# OSO-SWAT-A1-05.net
KiCad netlist of a schematic drawn in EAGLE
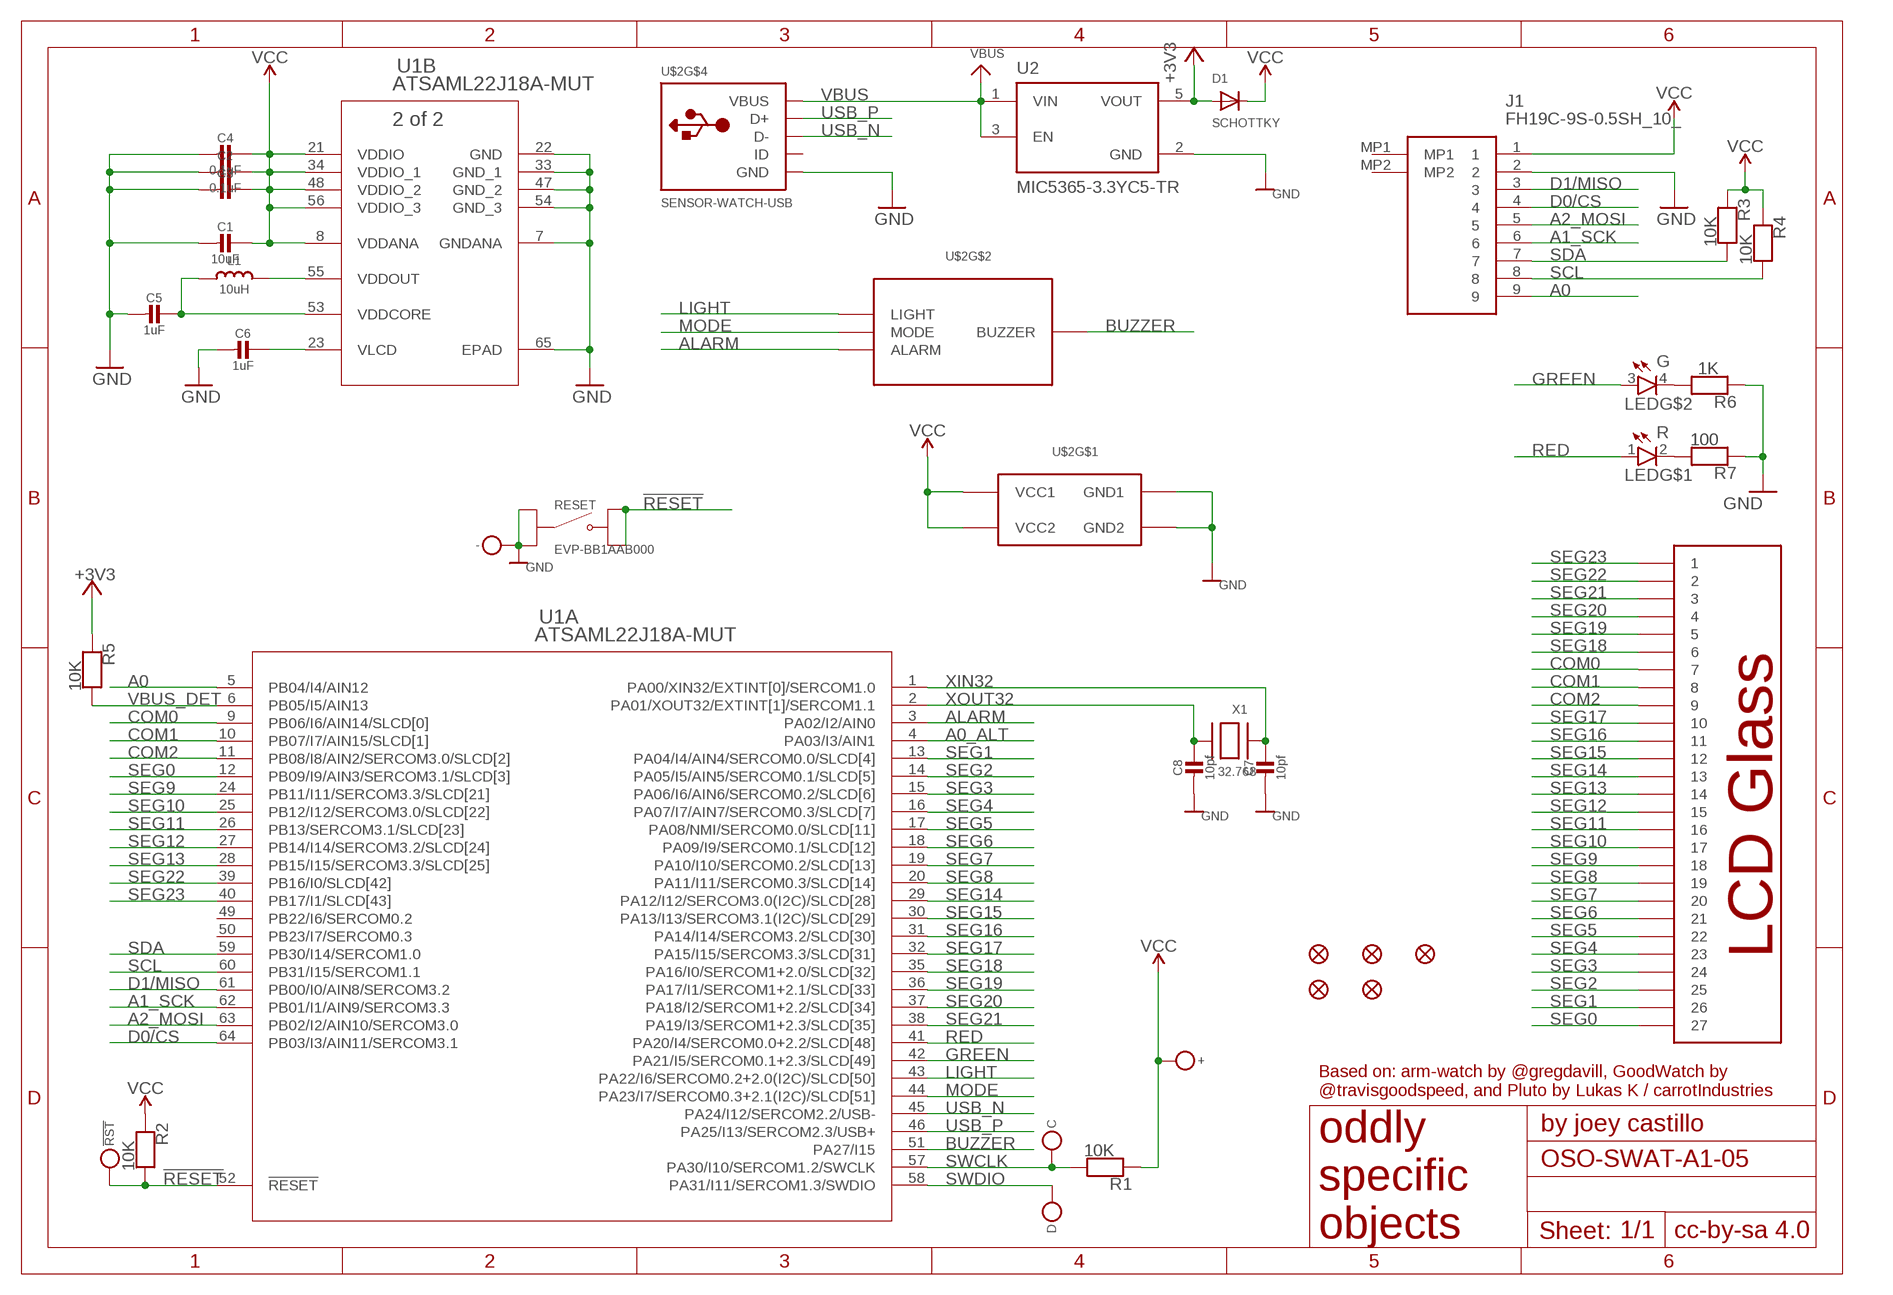
[diagram p0: schematic, sheet 1]

(export (version "E")
  (design (tool "Eeschema 10.0.6"))
  (components
    (comp (ref "!RST")
      (value "MICROBUILDER_TESTPOINTROUND1.5MM")
      (footprint "eagle-import:MICROBUILDER_TESTPOINT_ROUND_1.5MM")
      (libsource (lib "eagle-import") (part "MICROBUILDER_TESTPOINTROUND1.5MM"))
    )
    (comp (ref "+")
      (value "MICROBUILDER_TESTPOINTROUND1.5MM")
      (footprint "eagle-import:MICROBUILDER_TESTPOINT_ROUND_1.5MM")
      (libsource (lib "eagle-import") (part "MICROBUILDER_TESTPOINTROUND1.5MM"))
    )
    (comp (ref "-")
      (value "MICROBUILDER_TESTPOINTROUND1.5MM")
      (footprint "eagle-import:MICROBUILDER_TESTPOINT_ROUND_1.5MM")
      (libsource (lib "eagle-import") (part "MICROBUILDER_TESTPOINTROUND1.5MM"))
    )
    (comp (ref "C")
      (value "MICROBUILDER_TESTPOINTROUND1.5MM")
      (footprint "eagle-import:MICROBUILDER_TESTPOINT_ROUND_1.5MM")
      (libsource (lib "eagle-import") (part "MICROBUILDER_TESTPOINTROUND1.5MM"))
    )
    (comp (ref "C1")
      (value "10uF")
      (footprint "eagle-import:_0603MP")
      (libsource (lib "eagle-import") (part "CAP_CERAMIC_0603MP"))
    )
    (comp (ref "C2")
      (value "0.1uF")
      (footprint "eagle-import:_0603MP")
      (libsource (lib "eagle-import") (part "CAP_CERAMIC_0603MP"))
    )
    (comp (ref "C3")
      (value "0.1uF")
      (footprint "eagle-import:_0603MP")
      (libsource (lib "eagle-import") (part "CAP_CERAMIC_0603MP"))
    )
    (comp (ref "C4")
      (value "0.1uF")
      (footprint "eagle-import:_0603MP")
      (libsource (lib "eagle-import") (part "CAP_CERAMIC_0603MP"))
    )
    (comp (ref "C5")
      (value "1uF")
      (footprint "eagle-import:_0603MP")
      (libsource (lib "eagle-import") (part "CAP_CERAMIC_0603MP"))
    )
    (comp (ref "C6")
      (value "1uF")
      (footprint "eagle-import:_0603MP")
      (libsource (lib "eagle-import") (part "CAP_CERAMIC_0603MP"))
    )
    (comp (ref "C7")
      (value "10pf")
      (footprint "eagle-import:_0402MP")
      (libsource (lib "eagle-import") (part "CAP_CERAMIC_0402MP"))
    )
    (comp (ref "C8")
      (value "10pf")
      (footprint "eagle-import:_0402MP")
      (libsource (lib "eagle-import") (part "CAP_CERAMIC_0402MP"))
    )
    (comp (ref "D")
      (value "MICROBUILDER_TESTPOINTROUND1.5MM")
      (footprint "eagle-import:MICROBUILDER_TESTPOINT_ROUND_1.5MM")
      (libsource (lib "eagle-import") (part "MICROBUILDER_TESTPOINTROUND1.5MM"))
    )
    (comp (ref "D1")
      (value "SCHOTTKY")
      (footprint "eagle-import:SOD-323F")
      (libsource (lib "eagle-import") (part "DIODESOD-323F"))
    )
    (comp (ref "FID1")
      (value "FIDUCIAL_1MM")
      (footprint "eagle-import:FIDUCIAL_1MM")
      (libsource (lib "eagle-import") (part "FIDUCIAL_1MM"))
    )
    (comp (ref "FID2")
      (value "FIDUCIAL_1MM")
      (footprint "eagle-import:FIDUCIAL_1MM")
      (libsource (lib "eagle-import") (part "FIDUCIAL_1MM"))
    )
    (comp (ref "FID3")
      (value "FIDUCIAL_1MM")
      (footprint "eagle-import:FIDUCIAL_1MM")
      (fields (field (name "REV") "A"))
      (libsource (lib "eagle-import") (part "FIDUCIAL_1MM"))
    )
    (comp (ref "FID4")
      (value "FIDUCIAL_1MM")
      (footprint "eagle-import:FIDUCIAL_1MM")
      (libsource (lib "eagle-import") (part "FIDUCIAL_1MM"))
    )
    (comp (ref "FID6")
      (value "FIDUCIAL_1MM")
      (footprint "eagle-import:FIDUCIAL_1MM")
      (fields (field (name "REV") "A"))
      (libsource (lib "eagle-import") (part "FIDUCIAL_1MM"))
    )
    (comp (ref "J1")
      (value "FH19C-9S-0.5SH_10_")
      (footprint "eagle-import:FH19C9S05SH10")
      (fields
        (field (name "MANUFACTURER_PART_NUMBER") "FH19C-9S-0.5SH(10)")
        (field (name "MOUSER_PART_NUMBER") "798-FH19C9S05SH10")
      )
      (libsource (lib "eagle-import") (part "FH19C-9S-0.5SH_10_"))
    )
    (comp (ref "L1")
      (value "10uH")
      (footprint "eagle-import:MICROBUILDER__0805MP")
      (libsource (lib "eagle-import") (part "MICROBUILDER_INDUCTOR_0805MP"))
    )
    (comp (ref "LED")
      (value "QBLP655-RIG")
      (footprint "eagle-import:LED_QBLP655")
      (fields
        (field (name "DIGI-KEY_PART_NUMBER") "160-2026-1-ND")
        (field (name "MF") "Lite-On Inc.")
        (field (name "MP") "LTST-C235KGKRKT")
      )
      (libsource (lib "eagle-import") (part "QBLP655-RIG"))
    )
    (comp (ref "R1")
      (value "10K")
      (footprint "eagle-import:_0603MP")
      (libsource (lib "eagle-import") (part "RESISTOR_0603MP"))
    )
    (comp (ref "R2")
      (value "10K")
      (footprint "eagle-import:_0603MP")
      (libsource (lib "eagle-import") (part "RESISTOR_0603MP"))
    )
    (comp (ref "R3")
      (value "10K")
      (footprint "eagle-import:_0603MP")
      (libsource (lib "eagle-import") (part "RESISTOR_0603MP"))
    )
    (comp (ref "R4")
      (value "10K")
      (footprint "eagle-import:_0603MP")
      (libsource (lib "eagle-import") (part "RESISTOR_0603MP"))
    )
    (comp (ref "R5")
      (value "10K")
      (footprint "eagle-import:_0603MP")
      (libsource (lib "eagle-import") (part "RESISTOR_0603MP"))
    )
    (comp (ref "R6")
      (value "1K")
      (footprint "eagle-import:_0603MP")
      (libsource (lib "eagle-import") (part "RESISTOR_0603MP"))
    )
    (comp (ref "R7")
      (value "100")
      (footprint "eagle-import:_0603MP")
      (libsource (lib "eagle-import") (part "RESISTOR_0603MP"))
    )
    (comp (ref "RESET")
      (value "EVP-BB1AAB000")
      (footprint "eagle-import:SW_EVP-BB1AAB000")
      (fields
        (field (name "DIGI-KEY_PART_NUMBER") "P124390CT-ND")
        (field (name "MF") "Panasonic Electronic Components")
      )
      (libsource (lib "eagle-import") (part "EVP-BB1AAB000"))
    )
    (comp (ref "U$2")
      (value "SENSOR-WATCH-USB")
      (footprint "eagle-import:CASIO-F91W-OUTLINE-USB")
      (libsource (lib "eagle-import") (part "SENSOR-WATCH-USB"))
    )
    (comp (ref "U1")
      (value "ATSAML22J18A-MUT")
      (footprint "eagle-import:QFN64_9X9MC_MCH")
      (fields (field (name "COPYRIGHT") "Copyright (C) 2018 Accelerated Designs. All rights reserved"))
      (libsource (lib "eagle-import") (part "ATSAML22J18A-MUT"))
    )
    (comp (ref "U2")
      (value "MIC5365-3.3YC5-TR")
      (footprint "eagle-import:SOT65P210X110-5N")
      (fields (field (name "DIGI-KEY_PART_NUMBER") "576-3193-1-ND") (field (name "MF") "Microchip"))
      (libsource (lib "eagle-import") (part "MIC5365-3.3YC5-TR"))
    )
    (comp (ref "X1")
      (value "32.768")
      (footprint "eagle-import:XTAL3215")
      (libsource (lib "eagle-import") (part "XTAL-3.2X1.5"))
    )
  )
  (nets
    (net (code "1") (name "+3V3") (class "Default")
      (node (ref "D1") (pin "A") (pinfunction "A_A") (pintype "passive"))
      (node (ref "R5") (pin "1") (pinfunction "1_1") (pintype "passive"))
      (node (ref "U2") (pin "5") (pinfunction "VOUT_5") (pintype "output"))
    )
    (net (code "2") (name "/A0") (class "Default")
      (node (ref "J1") (pin "9") (pinfunction "9_9") (pintype "bidirectional"))
      (node (ref "U1") (pin "5") (pinfunction "PB04/I4/AIN12_5") (pintype "bidirectional"))
    )
    (net (code "3") (name "/A0_ALT") (class "Default")
      (node (ref "U1") (pin "4") (pinfunction "PA03/I3/AIN1_4") (pintype "bidirectional"))
    )
    (net (code "4") (name "/A1_SCK") (class "Default")
      (node (ref "J1") (pin "6") (pinfunction "6_6") (pintype "bidirectional"))
      (node (ref "U1") (pin "62") (pinfunction "PB01/I1/AIN9/SERCOM3.3_62") (pintype "bidirectional"))
    )
    (net (code "5") (name "/A2_MOSI") (class "Default")
      (node (ref "J1") (pin "5") (pinfunction "5_5") (pintype "bidirectional"))
      (node (ref "U1") (pin "63") (pinfunction "PB02/I2/AIN10/SERCOM3.0_63") (pintype "bidirectional"))
    )
    (net (code "6") (name "/ALARM") (class "Default")
      (node (ref "U$2") (pin "ALARM") (pinfunction "ALARM_ALARM") (pintype "bidirectional"))
      (node (ref "U1") (pin "3") (pinfunction "PA02/I2/AIN0_3") (pintype "bidirectional"))
    )
    (net (code "7") (name "/BUZZER") (class "Default")
      (node (ref "U$2") (pin "BUZZER") (pinfunction "BUZZER_BUZZER") (pintype "bidirectional"))
      (node (ref "U1") (pin "51") (pinfunction "PA27/I15_51") (pintype "bidirectional"))
    )
    (net (code "8") (name "/COM0") (class "Default")
      (node (ref "U$2") (pin "7") (pinfunction "7_7") (pintype "input"))
      (node (ref "U1") (pin "9") (pinfunction "PB06/I6/AIN14/SLCD[0]_9") (pintype "bidirectional"))
    )
    (net (code "9") (name "/COM1") (class "Default")
      (node (ref "U$2") (pin "8") (pinfunction "8_8") (pintype "input"))
      (node (ref "U1") (pin "10") (pinfunction "PB07/I7/AIN15/SLCD[1]_10") (pintype "bidirectional"))
    )
    (net (code "10") (name "/COM2") (class "Default")
      (node (ref "U$2") (pin "9") (pinfunction "9_9") (pintype "input"))
      (node (ref "U1") (pin "11") (pinfunction "PB08/I8/AIN2/SERCOM3.0/SLCD[2]_11") (pintype "bidirectional"))
    )
    (net (code "11") (name "/D0{slash}CS") (class "Default")
      (node (ref "J1") (pin "4") (pinfunction "4_4") (pintype "bidirectional"))
      (node (ref "U1") (pin "64") (pinfunction "PB03/I3/AIN11/SERCOM3.1_64") (pintype "bidirectional"))
    )
    (net (code "12") (name "/D1{slash}MISO") (class "Default")
      (node (ref "J1") (pin "3") (pinfunction "3_3") (pintype "bidirectional"))
      (node (ref "U1") (pin "61") (pinfunction "PB00/I0/AIN8/SERCOM3.2_61") (pintype "bidirectional"))
    )
    (net (code "13") (name "/GREEN") (class "Default")
      (node (ref "LED") (pin "3") (pinfunction "A_3") (pintype "passive"))
      (node (ref "U1") (pin "42") (pinfunction "PA21/I5/SERCOM0.1+2.3/SLCD[49]_42") (pintype "bidirectional"))
    )
    (net (code "14") (name "/LIGHT") (class "Default")
      (node (ref "U$2") (pin "LIGHT") (pinfunction "LIGHT_LIGHT") (pintype "bidirectional"))
      (node (ref "U1") (pin "43") (pinfunction "PA22/I6/SERCOM0.2+2.0(I2C)/SLCD[50]_43") (pintype "bidirectional"))
    )
    (net (code "15") (name "/MODE") (class "Default")
      (node (ref "U$2") (pin "MODE") (pinfunction "MODE_MODE") (pintype "bidirectional"))
      (node (ref "U1") (pin "44") (pinfunction "PA23/I7/SERCOM0.3+2.1(I2C)/SLCD[51]_44") (pintype "bidirectional"))
    )
    (net (code "16") (name "/RED") (class "Default")
      (node (ref "LED") (pin "1") (pinfunction "A_1") (pintype "passive"))
      (node (ref "U1") (pin "41") (pinfunction "PA20/I4/SERCOM0.0+2.2/SLCD[48]_41") (pintype "bidirectional"))
    )
    (net (code "17") (name "/SCL") (class "Default")
      (node (ref "J1") (pin "8") (pinfunction "8_8") (pintype "bidirectional"))
      (node (ref "R4") (pin "2") (pinfunction "2_2") (pintype "passive"))
      (node (ref "U1") (pin "60") (pinfunction "PB31/I15/SERCOM1.1_60") (pintype "bidirectional"))
    )
    (net (code "18") (name "/SDA") (class "Default")
      (node (ref "J1") (pin "7") (pinfunction "7_7") (pintype "bidirectional"))
      (node (ref "R3") (pin "2") (pinfunction "2_2") (pintype "passive"))
      (node (ref "U1") (pin "59") (pinfunction "PB30/I14/SERCOM1.0_59") (pintype "bidirectional"))
    )
    (net (code "19") (name "/SEG0") (class "Default")
      (node (ref "U$2") (pin "27") (pinfunction "27_27") (pintype "input"))
      (node (ref "U1") (pin "12") (pinfunction "PB09/I9/AIN3/SERCOM3.1/SLCD[3]_12") (pintype "bidirectional"))
    )
    (net (code "20") (name "/SEG1") (class "Default")
      (node (ref "U$2") (pin "26") (pinfunction "26_26") (pintype "input"))
      (node (ref "U1") (pin "13") (pinfunction "PA04/I4/AIN4/SERCOM0.0/SLCD[4]_13") (pintype "bidirectional"))
    )
    (net (code "21") (name "/SEG2") (class "Default")
      (node (ref "U$2") (pin "25") (pinfunction "25_25") (pintype "input"))
      (node (ref "U1") (pin "14") (pinfunction "PA05/I5/AIN5/SERCOM0.1/SLCD[5]_14") (pintype "bidirectional"))
    )
    (net (code "22") (name "/SEG3") (class "Default")
      (node (ref "U$2") (pin "24") (pinfunction "24_24") (pintype "input"))
      (node (ref "U1") (pin "15") (pinfunction "PA06/I6/AIN6/SERCOM0.2/SLCD[6]_15") (pintype "bidirectional"))
    )
    (net (code "23") (name "/SEG4") (class "Default")
      (node (ref "U$2") (pin "23") (pinfunction "23_23") (pintype "input"))
      (node (ref "U1") (pin "16") (pinfunction "PA07/I7/AIN7/SERCOM0.3/SLCD[7]_16") (pintype "bidirectional"))
    )
    (net (code "24") (name "/SEG5") (class "Default")
      (node (ref "U$2") (pin "22") (pinfunction "22_22") (pintype "input"))
      (node (ref "U1") (pin "17") (pinfunction "PA08/NMI/SERCOM0.0/SLCD[11]_17") (pintype "bidirectional"))
    )
    (net (code "25") (name "/SEG6") (class "Default")
      (node (ref "U$2") (pin "21") (pinfunction "21_21") (pintype "input"))
      (node (ref "U1") (pin "18") (pinfunction "PA09/I9/SERCOM0.1/SLCD[12]_18") (pintype "bidirectional"))
    )
    (net (code "26") (name "/SEG7") (class "Default")
      (node (ref "U$2") (pin "20") (pinfunction "20_20") (pintype "input"))
      (node (ref "U1") (pin "19") (pinfunction "PA10/I10/SERCOM0.2/SLCD[13]_19") (pintype "bidirectional"))
    )
    (net (code "27") (name "/SEG8") (class "Default")
      (node (ref "U$2") (pin "19") (pinfunction "19_19") (pintype "input"))
      (node (ref "U1") (pin "20") (pinfunction "PA11/I11/SERCOM0.3/SLCD[14]_20") (pintype "bidirectional"))
    )
    (net (code "28") (name "/SEG9") (class "Default")
      (node (ref "U$2") (pin "18") (pinfunction "18_18") (pintype "input"))
      (node (ref "U1") (pin "24") (pinfunction "PB11/I11/SERCOM3.3/SLCD[21]_24") (pintype "bidirectional"))
    )
    (net (code "29") (name "/SEG10") (class "Default")
      (node (ref "U$2") (pin "17") (pinfunction "17_17") (pintype "input"))
      (node (ref "U1") (pin "25") (pinfunction "PB12/I12/SERCOM3.0/SLCD[22]_25") (pintype "bidirectional"))
    )
    (net (code "30") (name "/SEG11") (class "Default")
      (node (ref "U$2") (pin "16") (pinfunction "16_16") (pintype "input"))
      (node (ref "U1") (pin "26") (pinfunction "PB13/SERCOM3.1/SLCD[23]_26") (pintype "bidirectional"))
    )
    (net (code "31") (name "/SEG12") (class "Default")
      (node (ref "U$2") (pin "15") (pinfunction "15_15") (pintype "input"))
      (node (ref "U1") (pin "27") (pinfunction "PB14/I14/SERCOM3.2/SLCD[24]_27") (pintype "bidirectional"))
    )
    (net (code "32") (name "/SEG13") (class "Default")
      (node (ref "U$2") (pin "14") (pinfunction "14_14") (pintype "input"))
      (node (ref "U1") (pin "28") (pinfunction "PB15/I15/SERCOM3.3/SLCD[25]_28") (pintype "bidirectional"))
    )
    (net (code "33") (name "/SEG14") (class "Default")
      (node (ref "U$2") (pin "13") (pinfunction "13_13") (pintype "input"))
      (node (ref "U1") (pin "29") (pinfunction "PA12/I12/SERCOM3.0(I2C)/SLCD[28]_29") (pintype "bidirectional"))
    )
    (net (code "34") (name "/SEG15") (class "Default")
      (node (ref "U$2") (pin "12") (pinfunction "12_12") (pintype "input"))
      (node (ref "U1") (pin "30") (pinfunction "PA13/I13/SERCOM3.1(I2C)/SLCD[29]_30") (pintype "bidirectional"))
    )
    (net (code "35") (name "/SEG16") (class "Default")
      (node (ref "U$2") (pin "11") (pinfunction "11_11") (pintype "input"))
      (node (ref "U1") (pin "31") (pinfunction "PA14/I14/SERCOM3.2/SLCD[30]_31") (pintype "bidirectional"))
    )
    (net (code "36") (name "/SEG17") (class "Default")
      (node (ref "U$2") (pin "10") (pinfunction "10_10") (pintype "input"))
      (node (ref "U1") (pin "32") (pinfunction "PA15/I15/SERCOM3.3/SLCD[31]_32") (pintype "bidirectional"))
    )
    (net (code "37") (name "/SEG18") (class "Default")
      (node (ref "U$2") (pin "6") (pinfunction "6_6") (pintype "input"))
      (node (ref "U1") (pin "35") (pinfunction "PA16/I0/SERCOM1+2.0/SLCD[32]_35") (pintype "bidirectional"))
    )
    (net (code "38") (name "/SEG19") (class "Default")
      (node (ref "U$2") (pin "5") (pinfunction "5_5") (pintype "input"))
      (node (ref "U1") (pin "36") (pinfunction "PA17/I1/SERCOM1+2.1/SLCD[33]_36") (pintype "bidirectional"))
    )
    (net (code "39") (name "/SEG20") (class "Default")
      (node (ref "U$2") (pin "4") (pinfunction "4_4") (pintype "input"))
      (node (ref "U1") (pin "37") (pinfunction "PA18/I2/SERCOM1+2.2/SLCD[34]_37") (pintype "bidirectional"))
    )
    (net (code "40") (name "/SEG21") (class "Default")
      (node (ref "U$2") (pin "3") (pinfunction "3_3") (pintype "input"))
      (node (ref "U1") (pin "38") (pinfunction "PA19/I3/SERCOM1+2.3/SLCD[35]_38") (pintype "bidirectional"))
    )
    (net (code "41") (name "/SEG22") (class "Default")
      (node (ref "U$2") (pin "2") (pinfunction "2_2") (pintype "input"))
      (node (ref "U1") (pin "39") (pinfunction "PB16/I0/SLCD[42]_39") (pintype "bidirectional"))
    )
    (net (code "42") (name "/SEG23") (class "Default")
      (node (ref "U$2") (pin "1") (pinfunction "1_1") (pintype "input"))
      (node (ref "U1") (pin "40") (pinfunction "PB17/I1/SLCD[43]_40") (pintype "bidirectional"))
    )
    (net (code "43") (name "/SWCLK") (class "Default")
      (node (ref "C") (pin "P$1") (pinfunction "P$1_P$1") (pintype "bidirectional"))
      (node (ref "R1") (pin "2") (pinfunction "2_2") (pintype "passive"))
      (node (ref "U1") (pin "57") (pinfunction "PA30/I10/SERCOM1.2/SWCLK_57") (pintype "bidirectional"))
    )
    (net (code "44") (name "/SWDIO") (class "Default")
      (node (ref "D") (pin "P$1") (pinfunction "P$1_P$1") (pintype "bidirectional"))
      (node (ref "U1") (pin "58") (pinfunction "PA31/I11/SERCOM1.3/SWDIO_58") (pintype "bidirectional"))
    )
    (net (code "45") (name "/USB_N") (class "Default")
      (node (ref "U$2") (pin "USB_N") (pinfunction "D-_USB_N") (pintype "bidirectional"))
      (node (ref "U1") (pin "45") (pinfunction "PA24/I12/SERCOM2.2/USB-_45") (pintype "bidirectional"))
    )
    (net (code "46") (name "/USB_P") (class "Default")
      (node (ref "U$2") (pin "USB_P") (pinfunction "D+_USB_P") (pintype "bidirectional"))
      (node (ref "U1") (pin "46") (pinfunction "PA25/I13/SERCOM2.3/USB+_46") (pintype "bidirectional"))
    )
    (net (code "47") (name "/VBUS_DET") (class "Default")
      (node (ref "R5") (pin "2") (pinfunction "2_2") (pintype "passive"))
      (node (ref "U1") (pin "6") (pinfunction "PB05/I5/AIN13_6") (pintype "bidirectional"))
    )
    (net (code "48") (name "/XIN32") (class "Default")
      (node (ref "C7") (pin "1") (pinfunction "1_1") (pintype "passive"))
      (node (ref "U1") (pin "1") (pinfunction "PA00/XIN32/EXTINT[0]/SERCOM1.0_1") (pintype "bidirectional"))
      (node (ref "X1") (pin "P$1") (pinfunction "P$1_P$1") (pintype "bidirectional"))
    )
    (net (code "49") (name "/XOUT32") (class "Default")
      (node (ref "C8") (pin "1") (pinfunction "1_1") (pintype "passive"))
      (node (ref "U1") (pin "2") (pinfunction "PA01/XOUT32/EXTINT[1]/SERCOM1.1_2") (pintype "bidirectional"))
      (node (ref "X1") (pin "P$2") (pinfunction "P$2_P$2") (pintype "bidirectional"))
    )
    (net (code "50") (name "/~{RESET}") (class "Default")
      (node (ref "!RST") (pin "P$1") (pinfunction "P$1_P$1") (pintype "bidirectional"))
      (node (ref "R2") (pin "2") (pinfunction "2_2") (pintype "passive"))
      (node (ref "RESET") (pin "B1") (pinfunction "B1_B1") (pintype "passive"))
      (node (ref "RESET") (pin "B2") (pinfunction "B2_B2") (pintype "passive"))
      (node (ref "U1") (pin "52") (pinfunction "~{RESET}_52") (pintype "bidirectional"))
    )
    (net (code "51") (name "GND") (class "Default")
      (node (ref "-") (pin "P$1") (pinfunction "P$1_P$1") (pintype "bidirectional"))
      (node (ref "C1") (pin "2") (pinfunction "2_2") (pintype "passive"))
      (node (ref "C2") (pin "2") (pinfunction "2_2") (pintype "passive"))
      (node (ref "C3") (pin "2") (pinfunction "2_2") (pintype "passive"))
      (node (ref "C4") (pin "2") (pinfunction "2_2") (pintype "passive"))
      (node (ref "C5") (pin "2") (pinfunction "2_2") (pintype "passive"))
      (node (ref "C6") (pin "2") (pinfunction "2_2") (pintype "passive"))
      (node (ref "C7") (pin "2") (pinfunction "2_2") (pintype "passive"))
      (node (ref "C8") (pin "2") (pinfunction "2_2") (pintype "passive"))
      (node (ref "J1") (pin "2") (pinfunction "2_2") (pintype "bidirectional"))
      (node (ref "R6") (pin "1") (pinfunction "1_1") (pintype "passive"))
      (node (ref "R7") (pin "1") (pinfunction "1_1") (pintype "passive"))
      (node (ref "RESET") (pin "A1") (pinfunction "A1_A1") (pintype "passive"))
      (node (ref "RESET") (pin "A2") (pinfunction "A2_A2") (pintype "passive"))
      (node (ref "U$2") (pin "GND") (pinfunction "GND_GND") (pintype "power_in"))
      (node (ref "U$2") (pin "GND1") (pinfunction "GND1_GND1") (pintype "bidirectional"))
      (node (ref "U$2") (pin "GND2") (pinfunction "GND2_GND2") (pintype "bidirectional"))
      (node (ref "U1") (pin "22") (pinfunction "GND_22") (pintype "passive"))
      (node (ref "U1") (pin "33") (pinfunction "GND_1_33") (pintype "passive"))
      (node (ref "U1") (pin "47") (pinfunction "GND_2_47") (pintype "passive"))
      (node (ref "U1") (pin "54") (pinfunction "GND_3_54") (pintype "passive"))
      (node (ref "U1") (pin "65") (pinfunction "EPAD_65") (pintype "passive"))
      (node (ref "U1") (pin "7") (pinfunction "GNDANA_7") (pintype "passive"))
      (node (ref "U2") (pin "2") (pinfunction "GND_2") (pintype "power_in"))
    )
    (net (code "52") (name "Net-(LEDA-C)") (class "Default")
      (node (ref "LED") (pin "2") (pinfunction "C_2") (pintype "passive"))
      (node (ref "R7") (pin "2") (pinfunction "2_2") (pintype "passive"))
    )
    (net (code "53") (name "Net-(LEDB-C)") (class "Default")
      (node (ref "LED") (pin "4") (pinfunction "C_4") (pintype "passive"))
      (node (ref "R6") (pin "2") (pinfunction "2_2") (pintype "passive"))
    )
    (net (code "54") (name "Net-(U1B-VDDCORE)") (class "Default")
      (node (ref "C5") (pin "1") (pinfunction "1_1") (pintype "passive"))
      (node (ref "L1") (pin "1") (pinfunction "1_1") (pintype "passive"))
      (node (ref "U1") (pin "53") (pinfunction "VDDCORE_53") (pintype "power_in"))
    )
    (net (code "55") (name "Net-(U1B-VDDOUT)") (class "Default")
      (node (ref "L1") (pin "2") (pinfunction "2_2") (pintype "passive"))
      (node (ref "U1") (pin "55") (pinfunction "VDDOUT_55") (pintype "output"))
    )
    (net (code "56") (name "Net-(U1B-VLCD)") (class "Default")
      (node (ref "C6") (pin "1") (pinfunction "1_1") (pintype "passive"))
      (node (ref "U1") (pin "23") (pinfunction "VLCD_23") (pintype "passive"))
    )
    (net (code "57") (name "VBUS") (class "Default")
      (node (ref "U$2") (pin "VBUS") (pinfunction "VBUS_VBUS") (pintype "power_in"))
      (node (ref "U2") (pin "1") (pinfunction "VIN_1") (pintype "input"))
      (node (ref "U2") (pin "3") (pinfunction "EN_3") (pintype "input"))
    )
    (net (code "58") (name "VCC") (class "Default")
      (node (ref "+") (pin "P$1") (pinfunction "P$1_P$1") (pintype "bidirectional"))
      (node (ref "C1") (pin "1") (pinfunction "1_1") (pintype "passive"))
      (node (ref "C2") (pin "1") (pinfunction "1_1") (pintype "passive"))
      (node (ref "C3") (pin "1") (pinfunction "1_1") (pintype "passive"))
      (node (ref "C4") (pin "1") (pinfunction "1_1") (pintype "passive"))
      (node (ref "D1") (pin "C") (pinfunction "C_C") (pintype "passive"))
      (node (ref "J1") (pin "1") (pinfunction "1_1") (pintype "bidirectional"))
      (node (ref "R1") (pin "1") (pinfunction "1_1") (pintype "passive"))
      (node (ref "R2") (pin "1") (pinfunction "1_1") (pintype "passive"))
      (node (ref "R3") (pin "1") (pinfunction "1_1") (pintype "passive"))
      (node (ref "R4") (pin "1") (pinfunction "1_1") (pintype "passive"))
      (node (ref "U$2") (pin "VCC1") (pinfunction "VCC1_VCC1") (pintype "bidirectional"))
      (node (ref "U$2") (pin "VCC2") (pinfunction "VCC2_VCC2") (pintype "bidirectional"))
      (node (ref "U1") (pin "21") (pinfunction "VDDIO_21") (pintype "power_in"))
      (node (ref "U1") (pin "34") (pinfunction "VDDIO_1_34") (pintype "power_in"))
      (node (ref "U1") (pin "48") (pinfunction "VDDIO_2_48") (pintype "power_in"))
      (node (ref "U1") (pin "56") (pinfunction "VDDIO_3_56") (pintype "power_in"))
      (node (ref "U1") (pin "8") (pinfunction "VDDANA_8") (pintype "power_in"))
    )
    (net (code "59") (name "unconnected-(J1-PadMP1)") (class "Default")
      (node (ref "J1") (pin "MP1") (pinfunction "MP1_MP1") (pintype "bidirectional"))
    )
    (net (code "60") (name "unconnected-(J1-PadMP2)") (class "Default")
      (node (ref "J1") (pin "MP2") (pinfunction "MP2_MP2") (pintype "bidirectional"))
    )
    (net (code "61") (name "unconnected-(U$2D-ID-PadUSB_ID)") (class "Default")
      (node (ref "U$2") (pin "USB_ID") (pinfunction "ID_USB_ID") (pintype "bidirectional"))
    )
    (net (code "62") (name "unconnected-(U1A-PB22{slash}I6{slash}SERCOM0.2-Pad49)") (class "Default")
      (node (ref "U1") (pin "49") (pinfunction "PB22/I6/SERCOM0.2_49") (pintype "bidirectional"))
    )
    (net (code "63") (name "unconnected-(U1A-PB23{slash}I7{slash}SERCOM0.3-Pad50)") (class "Default")
      (node (ref "U1") (pin "50") (pinfunction "PB23/I7/SERCOM0.3_50") (pintype "bidirectional"))
    )
  )
)
